# electron_v009.net
KiCad netlist of a schematic drawn in EAGLE
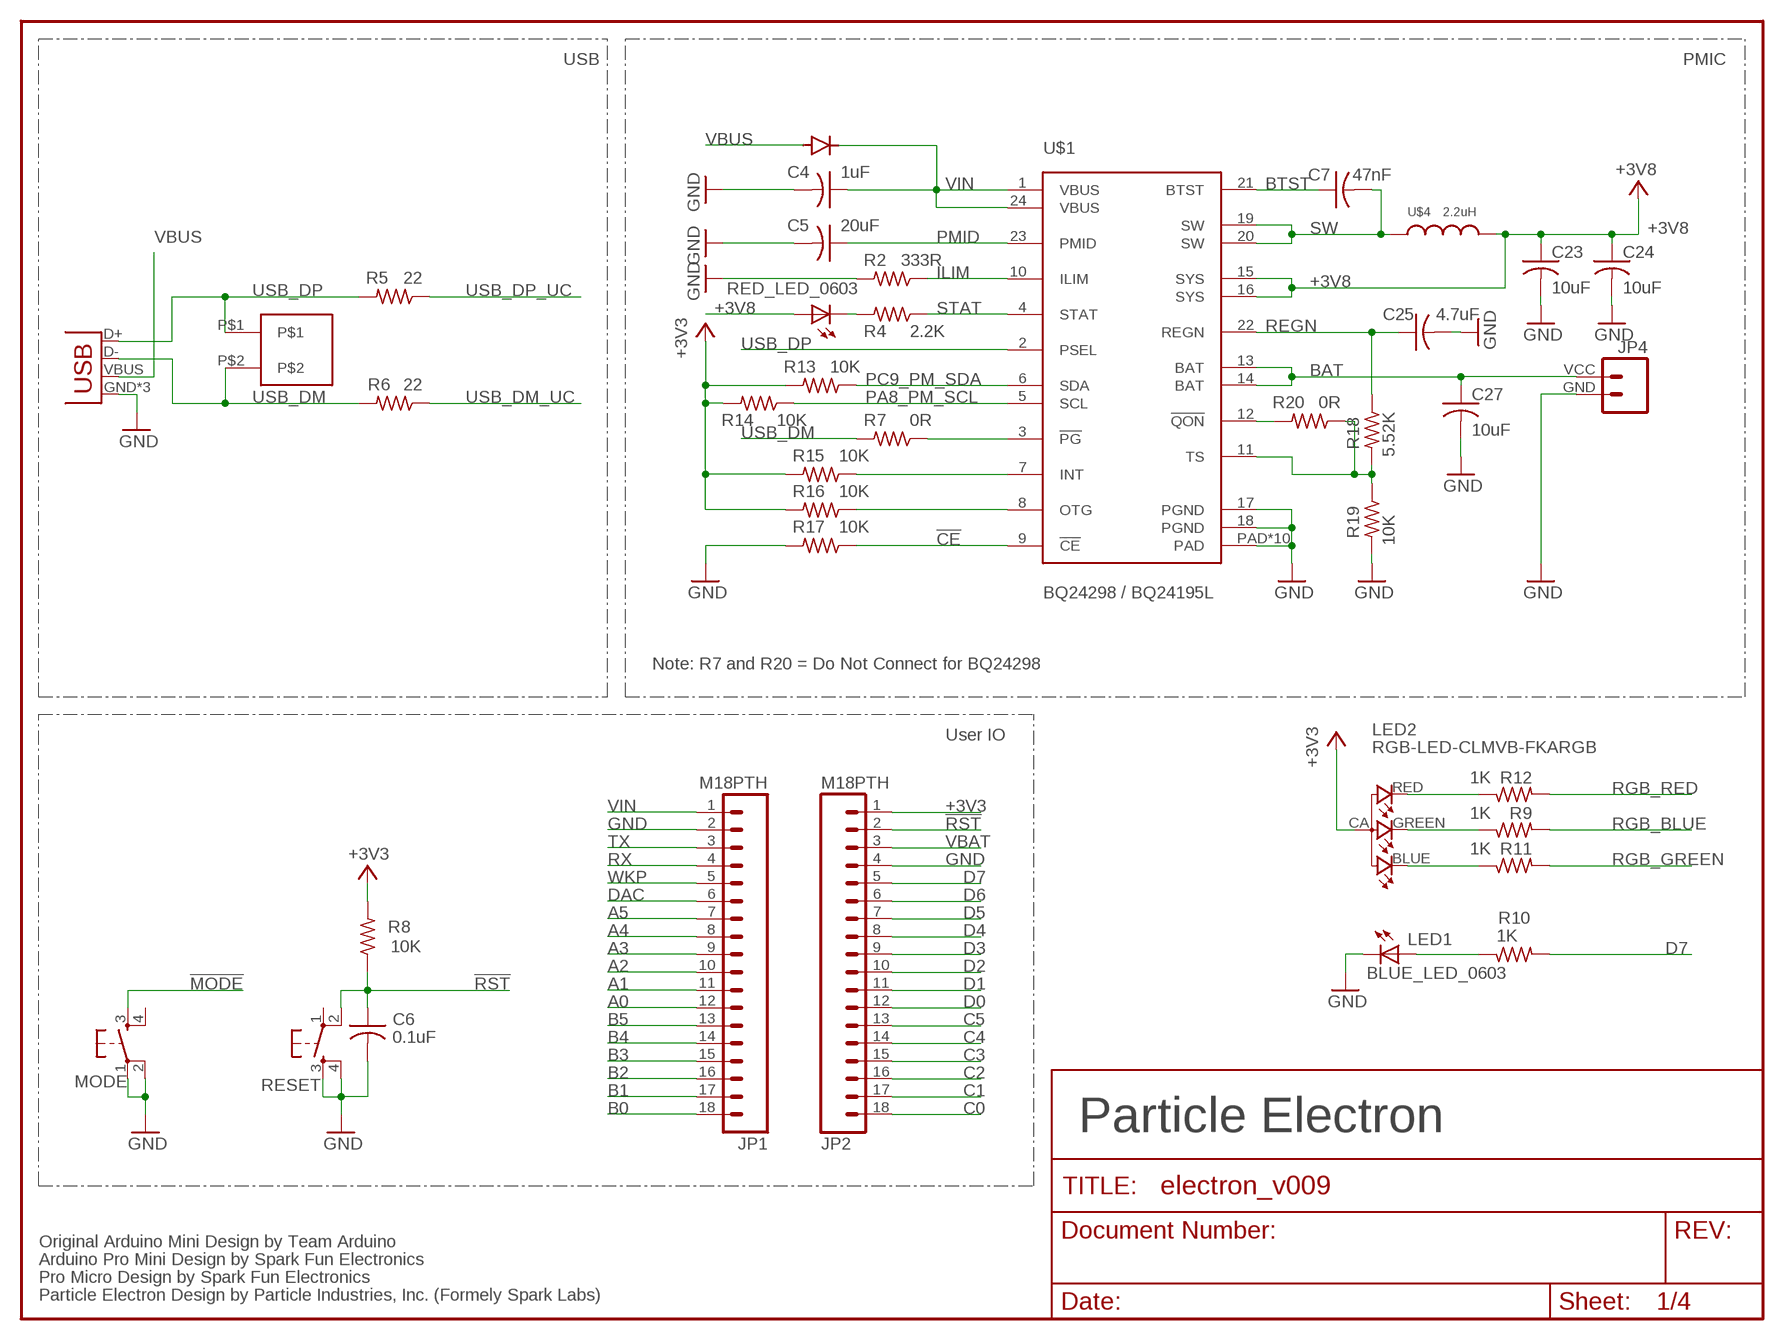
[diagram p0: schematic, sheet 1]
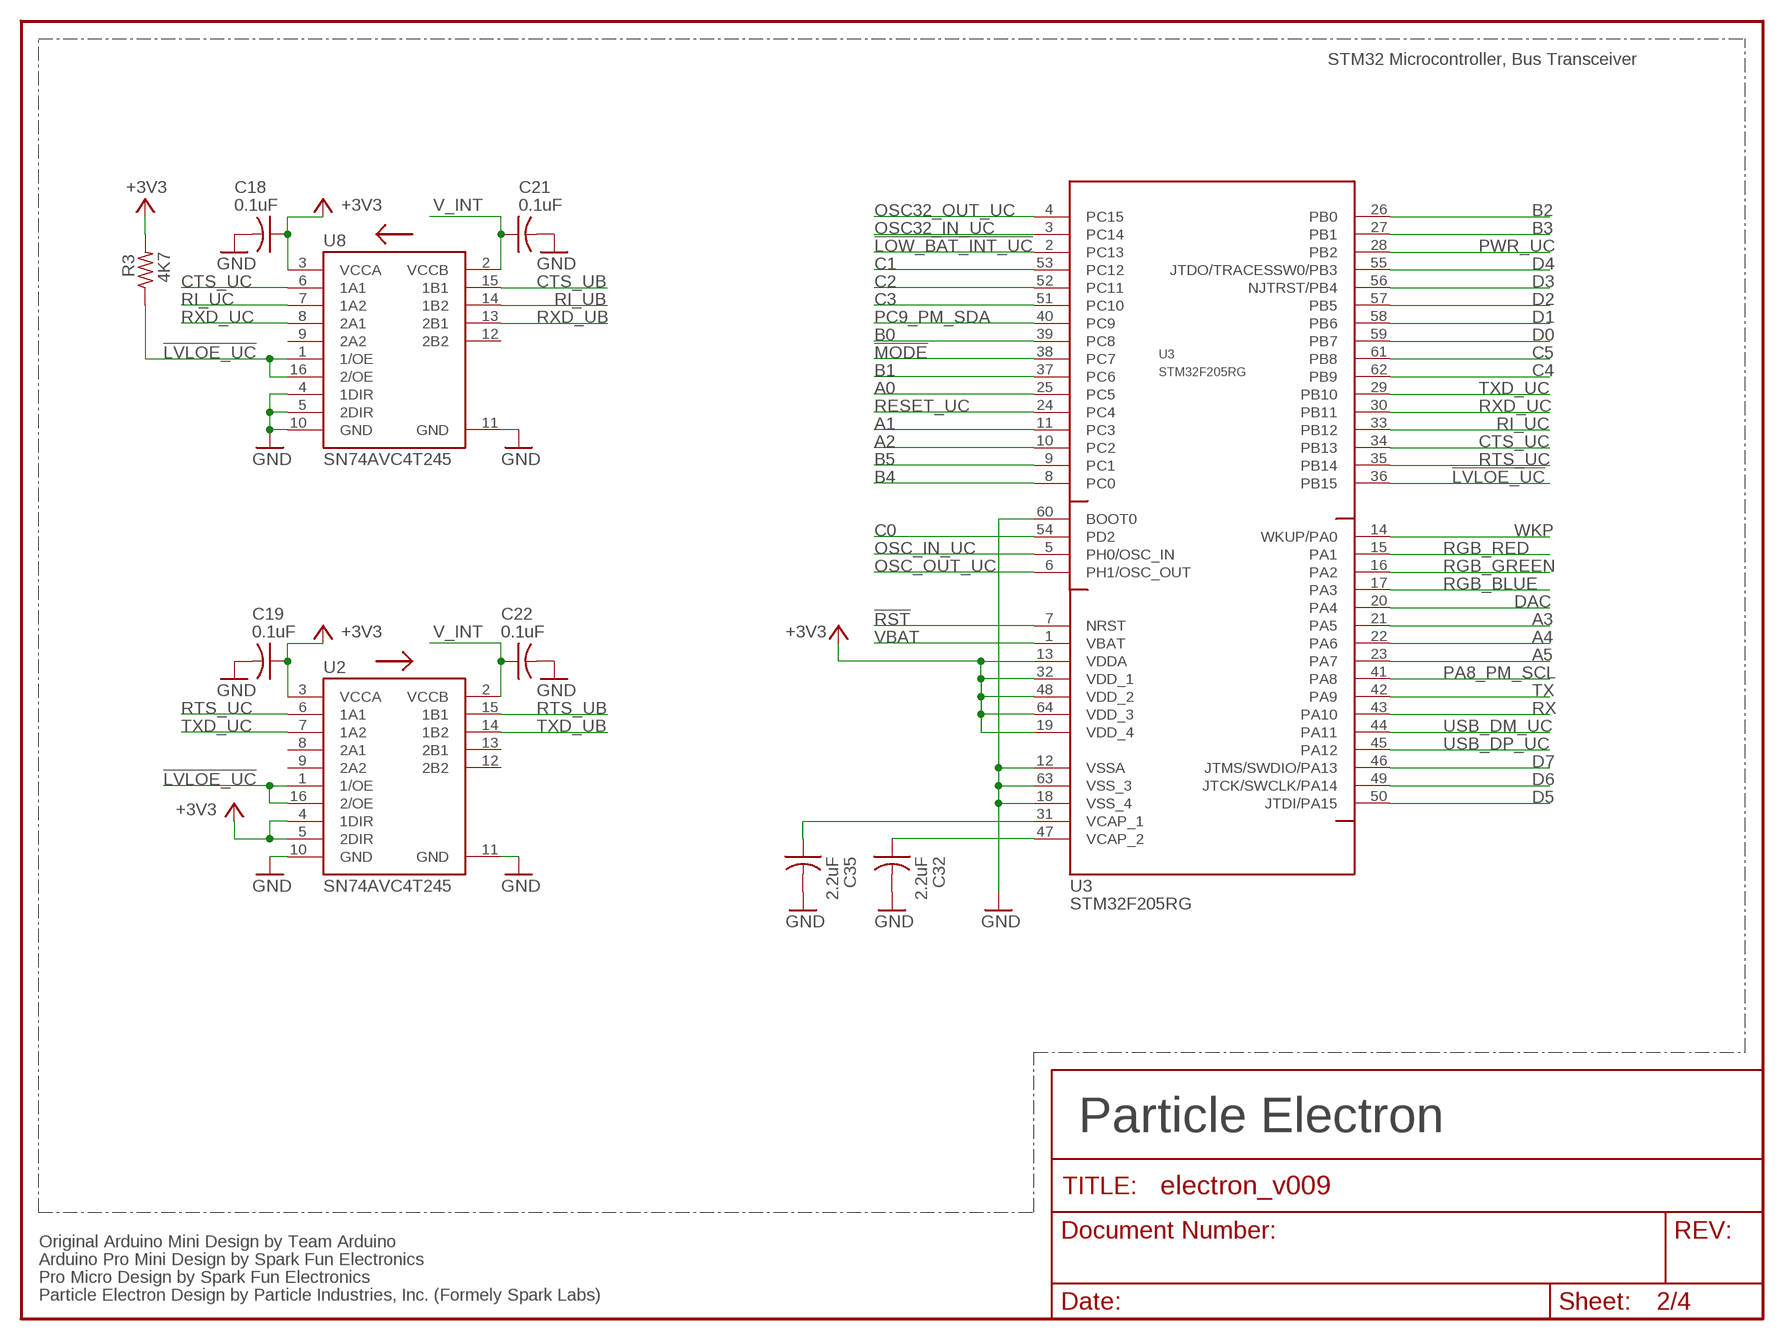
[diagram p1: schematic, sheet 2]
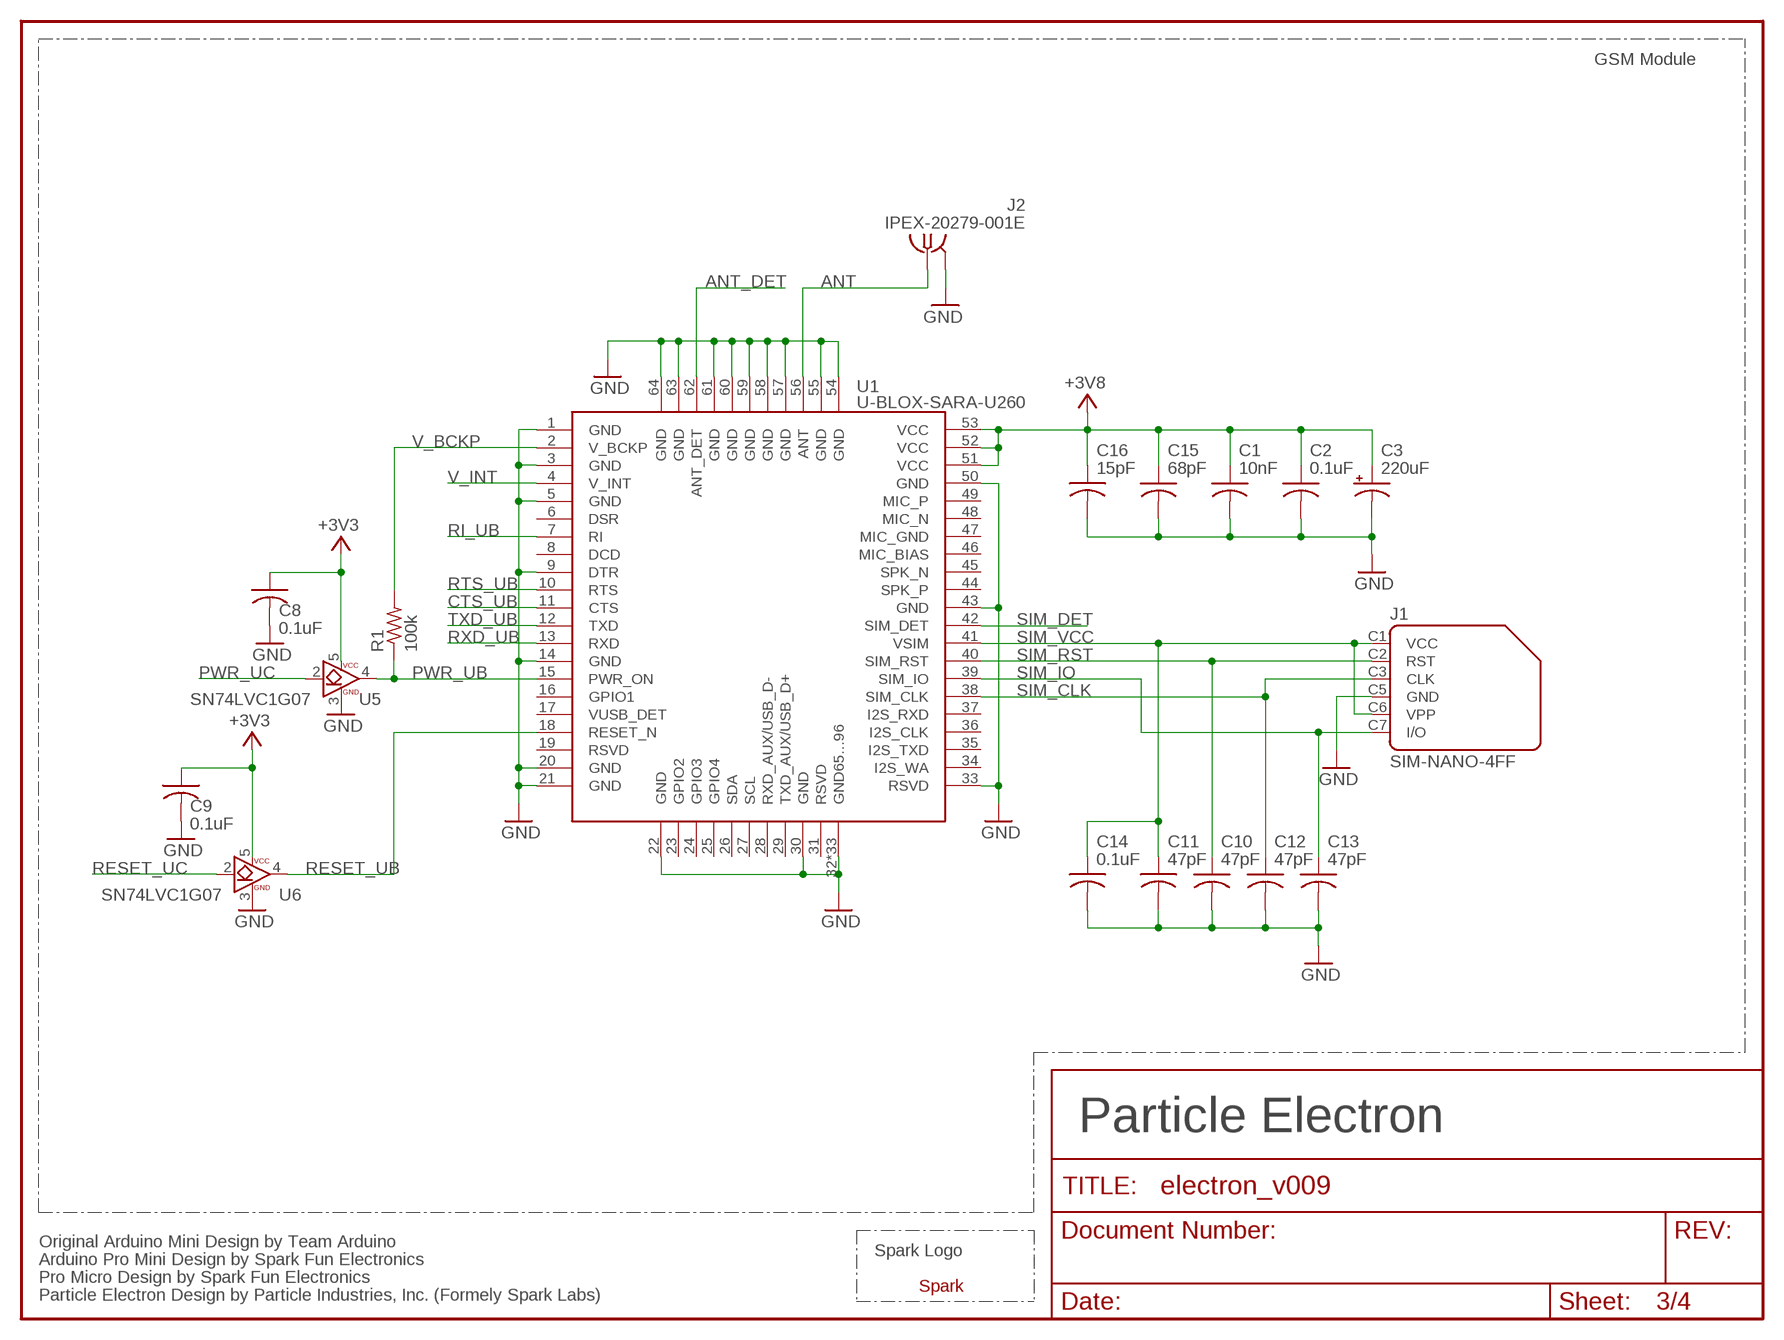
[diagram p2: schematic, sheet 3]
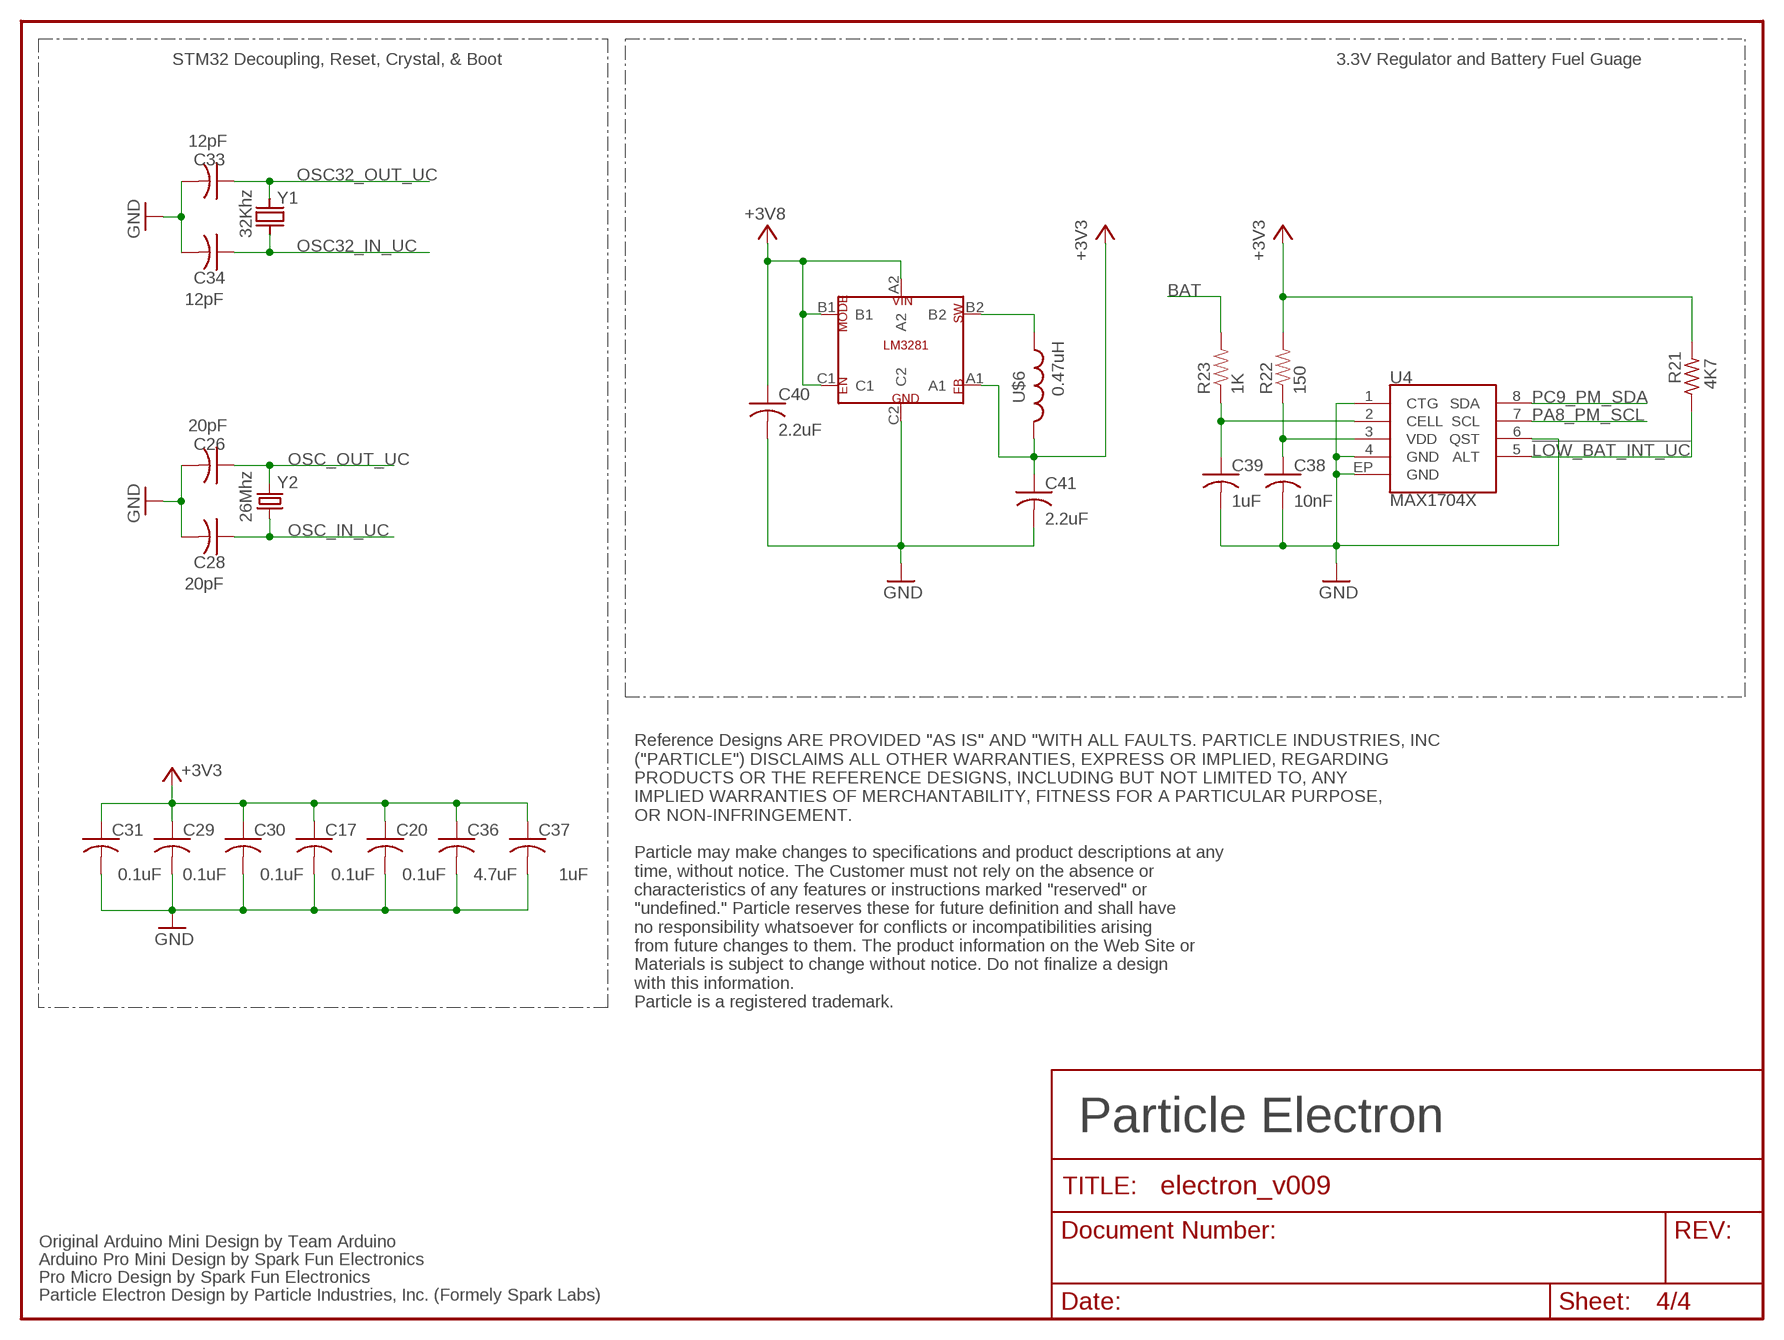
[diagram p3: schematic, sheet 4]

(export (version "E")
  (design (tool "Eeschema 10.0.6"))
  (components
    (comp (ref "C17")
      (value "0.1uF")
      (footprint "eagle-import:C0402_B")
      (libsource (lib "eagle-import") (part "C-US"))
    )
    (comp (ref "C20")
      (value "0.1uF")
      (footprint "eagle-import:C0402_B")
      (libsource (lib "eagle-import") (part "C-US"))
    )
    (comp (ref "C26")
      (value "20pF")
      (footprint "eagle-import:C0402_B")
      (libsource (lib "eagle-import") (part "C-US"))
    )
    (comp (ref "C28")
      (value "20pF")
      (footprint "eagle-import:C0402_B")
      (libsource (lib "eagle-import") (part "C-US"))
    )
    (comp (ref "C29")
      (value "0.1uF")
      (footprint "eagle-import:C0402_B")
      (libsource (lib "eagle-import") (part "C-US"))
    )
    (comp (ref "C30")
      (value "0.1uF")
      (footprint "eagle-import:C0402_B")
      (libsource (lib "eagle-import") (part "C-US"))
    )
    (comp (ref "C31")
      (value "0.1uF")
      (footprint "eagle-import:C0402_B")
      (libsource (lib "eagle-import") (part "C-US"))
    )
    (comp (ref "C33")
      (value "12pF")
      (footprint "eagle-import:C0402_B")
      (libsource (lib "eagle-import") (part "C-US"))
    )
    (comp (ref "C34")
      (value "12pF")
      (footprint "eagle-import:C0402_B")
      (libsource (lib "eagle-import") (part "C-US"))
    )
    (comp (ref "C36")
      (value "4.7uF")
      (footprint "eagle-import:C0402_B")
      (libsource (lib "eagle-import") (part "C-US"))
    )
    (comp (ref "C37")
      (value "1uF")
      (footprint "eagle-import:C0402_B")
      (libsource (lib "eagle-import") (part "C-US"))
    )
    (comp (ref "C38")
      (value "10nF")
      (footprint "eagle-import:C0402_B")
      (libsource (lib "eagle-import") (part "C-US"))
    )
    (comp (ref "C39")
      (value "1uF")
      (footprint "eagle-import:C0402_B")
      (libsource (lib "eagle-import") (part "C-US"))
    )
    (comp (ref "C40")
      (value "2.2uF")
      (footprint "eagle-import:C0603_B")
      (libsource (lib "eagle-import") (part "C-US0603"))
    )
    (comp (ref "C41")
      (value "2.2uF")
      (footprint "eagle-import:C0603_B")
      (libsource (lib "eagle-import") (part "C-US0603"))
    )
    (comp (ref "R21")
      (value "4K7")
      (footprint "eagle-import:R0402_B")
      (libsource (lib "eagle-import") (part "R-US_"))
    )
    (comp (ref "R22")
      (value "150")
      (footprint "eagle-import:0603-RES")
      (libsource (lib "eagle-import") (part "RESISTOR0603-RES"))
    )
    (comp (ref "R23")
      (value "1K")
      (footprint "eagle-import:0603-RES")
      (libsource (lib "eagle-import") (part "RESISTOR0603-RES"))
    )
    (comp (ref "U$5")
      (value "LM3281_DSBGA")
      (footprint "eagle-import:DSBGA")
      (libsource (lib "eagle-import") (part "LM3281_DSBGA"))
    )
    (comp (ref "U$6")
      (value "0.47uH")
      (footprint "eagle-import:0805")
      (libsource (lib "eagle-import") (part "INDUCTOR0805"))
    )
    (comp (ref "U4")
      (value "MAX1704X")
      (footprint "eagle-import:TDFN-8")
      (libsource (lib "eagle-import") (part "MAX1704X"))
    )
    (comp (ref "Y1")
      (value "32Khz")
      (footprint "eagle-import:FC135")
      (libsource (lib "eagle-import") (part "Q_FC135"))
    )
    (comp (ref "Y2")
      (value "26Mhz")
      (footprint "eagle-import:CRYSTAL-SMD-5X3")
      (libsource (lib "eagle-import") (part "CRYSTAL5X3"))
    )
    (comp (ref "C1")
      (value "10nF")
      (footprint "eagle-import:C0402_B")
      (libsource (lib "eagle-import") (part "C-US"))
    )
    (comp (ref "C2")
      (value "0.1uF")
      (footprint "eagle-import:C0402_B")
      (libsource (lib "eagle-import") (part "C-US"))
    )
    (comp (ref "C3")
      (value "220uF")
      (footprint "eagle-import:C_6032-28R")
      (libsource (lib "eagle-import") (part "CPOL-USC/6032-28R"))
    )
    (comp (ref "C8")
      (value "0.1uF")
      (footprint "eagle-import:C0402_B")
      (libsource (lib "eagle-import") (part "C-US"))
    )
    (comp (ref "C9")
      (value "0.1uF")
      (footprint "eagle-import:C0402_B")
      (libsource (lib "eagle-import") (part "C-US"))
    )
    (comp (ref "C10")
      (value "47pF")
      (footprint "eagle-import:C0402_B")
      (libsource (lib "eagle-import") (part "C-US"))
    )
    (comp (ref "C11")
      (value "47pF")
      (footprint "eagle-import:C0402_B")
      (libsource (lib "eagle-import") (part "C-US"))
    )
    (comp (ref "C12")
      (value "47pF")
      (footprint "eagle-import:C0402_B")
      (libsource (lib "eagle-import") (part "C-US"))
    )
    (comp (ref "C13")
      (value "47pF")
      (footprint "eagle-import:C0402_B")
      (libsource (lib "eagle-import") (part "C-US"))
    )
    (comp (ref "C14")
      (value "0.1uF")
      (footprint "eagle-import:C0402_B")
      (libsource (lib "eagle-import") (part "C-US"))
    )
    (comp (ref "C15")
      (value "68pF")
      (footprint "eagle-import:C0402_B")
      (libsource (lib "eagle-import") (part "C-US"))
    )
    (comp (ref "C16")
      (value "15pF")
      (footprint "eagle-import:C0402_B")
      (libsource (lib "eagle-import") (part "C-US"))
    )
    (comp (ref "J1")
      (value "SIM-NANO-4FF")
      (footprint "eagle-import:GCT-SIM8100")
      (libsource (lib "eagle-import") (part "SIM-NANO-4FF"))
    )
    (comp (ref "J2")
      (value "IPEX-20279-001E")
      (footprint "eagle-import:IPEX-20279-001E")
      (libsource (lib "eagle-import") (part "IPEX-20279-001E"))
    )
    (comp (ref "R1")
      (value "100k")
      (footprint "eagle-import:R0402_B")
      (libsource (lib "eagle-import") (part "R-US_"))
    )
    (comp (ref "U$2")
      (value "SPARK_LOGO2")
      (footprint "eagle-import:SPARK_LOGO2")
      (libsource (lib "eagle-import") (part "SPARK_LOGO2"))
    )
    (comp (ref "U1")
      (value "U-BLOX-SARA-U260")
      (footprint "eagle-import:U-BLOX-SARA-U2")
      (libsource (lib "eagle-import") (part "U-BLOX-SARA-U260"))
    )
    (comp (ref "U5")
      (value "SN74LVC1G07")
      (footprint "eagle-import:SC-70-5")
      (libsource (lib "eagle-import") (part "SN74LVC1G07"))
    )
    (comp (ref "U6")
      (value "SN74LVC1G07")
      (footprint "eagle-import:SC-70-5")
      (libsource (lib "eagle-import") (part "SN74LVC1G07"))
    )
    (comp (ref "C18")
      (value "0.1uF")
      (footprint "eagle-import:C0402_B")
      (libsource (lib "eagle-import") (part "C-US"))
    )
    (comp (ref "C19")
      (value "0.1uF")
      (footprint "eagle-import:C0402_B")
      (libsource (lib "eagle-import") (part "C-US"))
    )
    (comp (ref "C21")
      (value "0.1uF")
      (footprint "eagle-import:C0402_B")
      (libsource (lib "eagle-import") (part "C-US"))
    )
    (comp (ref "C22")
      (value "0.1uF")
      (footprint "eagle-import:C0402_B")
      (libsource (lib "eagle-import") (part "C-US"))
    )
    (comp (ref "C32")
      (value "2.2uF")
      (footprint "eagle-import:C0402_B")
      (libsource (lib "eagle-import") (part "C-US"))
    )
    (comp (ref "C35")
      (value "2.2uF")
      (footprint "eagle-import:C0402_B")
      (libsource (lib "eagle-import") (part "C-US"))
    )
    (comp (ref "R3")
      (value "4K7")
      (footprint "eagle-import:R0402_B")
      (libsource (lib "eagle-import") (part "R-US_"))
    )
    (comp (ref "U2")
      (value "SN74AVC4T245")
      (footprint "eagle-import:UFQFN-16")
      (libsource (lib "eagle-import") (part "SN74AVC4T245"))
    )
    (comp (ref "U3")
      (value "STM32F205RG")
      (footprint "eagle-import:LQFP64")
      (libsource (lib "eagle-import") (part "STM32F20XR"))
    )
    (comp (ref "U8")
      (value "SN74AVC4T245")
      (footprint "eagle-import:UFQFN-16")
      (libsource (lib "eagle-import") (part "SN74AVC4T245"))
    )
    (comp (ref "BLUE_LED_0603")
      (value "LED0603")
      (footprint "eagle-import:LED-0603")
      (libsource (lib "eagle-import") (part "LED0603"))
    )
    (comp (ref "C4")
      (value "1uF")
      (footprint "eagle-import:C0603_B")
      (libsource (lib "eagle-import") (part "C-US0603"))
    )
    (comp (ref "C5")
      (value "20uF")
      (footprint "eagle-import:C0603_B")
      (libsource (lib "eagle-import") (part "C-US0603"))
    )
    (comp (ref "C6")
      (value "0.1uF")
      (footprint "eagle-import:C0402_B")
      (libsource (lib "eagle-import") (part "C-US"))
    )
    (comp (ref "C7")
      (value "47nF")
      (footprint "eagle-import:C0402_B")
      (libsource (lib "eagle-import") (part "C-US"))
    )
    (comp (ref "C23")
      (value "10uF")
      (footprint "eagle-import:C0603_B")
      (libsource (lib "eagle-import") (part "C-US0603"))
    )
    (comp (ref "C24")
      (value "10uF")
      (footprint "eagle-import:C0603_B")
      (libsource (lib "eagle-import") (part "C-US0603"))
    )
    (comp (ref "C25")
      (value "4.7uF")
      (footprint "eagle-import:C0603_B")
      (libsource (lib "eagle-import") (part "C-US0603"))
    )
    (comp (ref "C27")
      (value "10uF")
      (footprint "eagle-import:C0603_B")
      (libsource (lib "eagle-import") (part "C-US0603"))
    )
    (comp (ref "JP1")
      (value "M18PTH")
      (footprint "eagle-import:1X18-SMALL-PADS")
      (libsource (lib "eagle-import") (part "M18PTH"))
    )
    (comp (ref "JP2")
      (value "M18PTH")
      (footprint "eagle-import:1X18-SMALL-PADS")
      (libsource (lib "eagle-import") (part "M18PTH"))
    )
    (comp (ref "JP4")
      (value "M024UCON-15767")
      (footprint "eagle-import:JST-2-SMD-VERT")
      (libsource (lib "eagle-import") (part "M024UCON-15767"))
    )
    (comp (ref "LED2")
      (value "RGB-LED-CLMVB-FKARGB")
      (footprint "eagle-import:PLCC4-2MM-RGB")
      (libsource (lib "eagle-import") (part "RGB-LED-CLMVB-FKARGB"))
    )
    (comp (ref "MODE")
      (value "KMR211GLFS")
      (footprint "eagle-import:TACTILE_SWITCH_SMD")
      (libsource (lib "eagle-import") (part "TAC_SWITCHSMD"))
    )
    (comp (ref "R2")
      (value "333R")
      (footprint "eagle-import:R0402_B")
      (libsource (lib "eagle-import") (part "R-US_"))
    )
    (comp (ref "R4")
      (value "2.2K")
      (footprint "eagle-import:R0402_B")
      (libsource (lib "eagle-import") (part "R-US_"))
    )
    (comp (ref "R5")
      (value "22")
      (footprint "eagle-import:R0402_B")
      (libsource (lib "eagle-import") (part "R-US_"))
    )
    (comp (ref "R6")
      (value "22")
      (footprint "eagle-import:R0402_B")
      (libsource (lib "eagle-import") (part "R-US_"))
    )
    (comp (ref "R7")
      (value "0R")
      (footprint "eagle-import:R0402_B")
      (libsource (lib "eagle-import") (part "R-US_"))
    )
    (comp (ref "R8")
      (value "10K")
      (footprint "eagle-import:R0402_B")
      (libsource (lib "eagle-import") (part "R-US_"))
    )
    (comp (ref "R9")
      (value "1K")
      (footprint "eagle-import:R0402_B")
      (libsource (lib "eagle-import") (part "R-US_"))
    )
    (comp (ref "R10")
      (value "1K")
      (footprint "eagle-import:R0402_B")
      (libsource (lib "eagle-import") (part "R-US_"))
    )
    (comp (ref "R11")
      (value "1K")
      (footprint "eagle-import:R0402_B")
      (libsource (lib "eagle-import") (part "R-US_"))
    )
    (comp (ref "R12")
      (value "1K")
      (footprint "eagle-import:R0402_B")
      (libsource (lib "eagle-import") (part "R-US_"))
    )
    (comp (ref "R13")
      (value "10K")
      (footprint "eagle-import:R0402_B")
      (libsource (lib "eagle-import") (part "R-US_"))
    )
    (comp (ref "R14")
      (value "10K")
      (footprint "eagle-import:R0402_B")
      (libsource (lib "eagle-import") (part "R-US_"))
    )
    (comp (ref "R15")
      (value "10K")
      (footprint "eagle-import:R0402_B")
      (libsource (lib "eagle-import") (part "R-US_"))
    )
    (comp (ref "R16")
      (value "10K")
      (footprint "eagle-import:R0402_B")
      (libsource (lib "eagle-import") (part "R-US_"))
    )
    (comp (ref "R17")
      (value "10K")
      (footprint "eagle-import:R0402_B")
      (libsource (lib "eagle-import") (part "R-US_"))
    )
    (comp (ref "R18")
      (value "5.52K")
      (footprint "eagle-import:R0402_B")
      (libsource (lib "eagle-import") (part "R-US_"))
    )
    (comp (ref "R19")
      (value "10K")
      (footprint "eagle-import:R0402_B")
      (libsource (lib "eagle-import") (part "R-US_"))
    )
    (comp (ref "R20")
      (value "0R")
      (footprint "eagle-import:R0402_B")
      (libsource (lib "eagle-import") (part "R-US_"))
    )
    (comp (ref "RED_LED_0603")
      (value "LED0603")
      (footprint "eagle-import:LED-0603")
      (libsource (lib "eagle-import") (part "LED0603"))
    )
    (comp (ref "RESET")
      (value "KMR211GLFS")
      (footprint "eagle-import:TACTILE_SWITCH_SMD")
      (libsource (lib "eagle-import") (part "TAC_SWITCHSMD"))
    )
    (comp (ref "U$1")
      (value "BQ24298 / BQ24195L")
      (footprint "eagle-import:QFN24")
      (libsource (lib "eagle-import") (part "BQ24298RTWR"))
    )
    (comp (ref "U$3")
      (value "DIODE")
      (footprint "eagle-import:DIODE-DO-220AA(SMP)")
      (libsource (lib "eagle-import") (part "DIODE"))
    )
    (comp (ref "U$4")
      (value "2.2uH")
      (footprint "eagle-import:4020TYPE")
      (libsource (lib "eagle-import") (part "INDUCTOR4020"))
    )
    (comp (ref "U$7")
      (value "M02_0.05_HEADER")
      (footprint "eagle-import:M02_0.05_HEADER")
      (libsource (lib "eagle-import") (part "M02_0.05_HEADER"))
    )
    (comp (ref "X1")
      (value "USB-MICROB")
      (footprint "eagle-import:USB-MICROB-SLOT-HOLE")
      (libsource (lib "eagle-import") (part "USBUSB-MICROB-SLOT-HOLE"))
    )
  )
  (nets
    (net (code "1") (name "+3V3") (class "Default")
      (node (ref "C17") (pin "1") (pinfunction "1_1") (pintype "passive"))
      (node (ref "C18") (pin "1") (pinfunction "1_1") (pintype "passive"))
      (node (ref "C19") (pin "1") (pinfunction "1_1") (pintype "passive"))
      (node (ref "C20") (pin "1") (pinfunction "1_1") (pintype "passive"))
      (node (ref "C29") (pin "1") (pinfunction "1_1") (pintype "passive"))
      (node (ref "C30") (pin "1") (pinfunction "1_1") (pintype "passive"))
      (node (ref "C31") (pin "1") (pinfunction "1_1") (pintype "passive"))
      (node (ref "C36") (pin "1") (pinfunction "1_1") (pintype "passive"))
      (node (ref "C37") (pin "1") (pinfunction "1_1") (pintype "passive"))
      (node (ref "C41") (pin "1") (pinfunction "1_1") (pintype "passive"))
      (node (ref "C8") (pin "1") (pinfunction "1_1") (pintype "passive"))
      (node (ref "C9") (pin "1") (pinfunction "1_1") (pintype "passive"))
      (node (ref "JP2") (pin "1") (pinfunction "1_1") (pintype "passive"))
      (node (ref "LED2") (pin "CA") (pinfunction "1_CA") (pintype "passive"))
      (node (ref "R13") (pin "2") (pinfunction "2_2") (pintype "passive"))
      (node (ref "R14") (pin "2") (pinfunction "2_2") (pintype "passive"))
      (node (ref "R15") (pin "2") (pinfunction "2_2") (pintype "passive"))
      (node (ref "R16") (pin "2") (pinfunction "2_2") (pintype "passive"))
      (node (ref "R21") (pin "2") (pinfunction "2_2") (pintype "passive"))
      (node (ref "R22") (pin "2") (pinfunction "2_2") (pintype "passive"))
      (node (ref "R3") (pin "2") (pinfunction "2_2") (pintype "passive"))
      (node (ref "R8") (pin "2") (pinfunction "2_2") (pintype "passive"))
      (node (ref "U$5") (pin "A1") (pinfunction "A1_A1") (pintype "bidirectional"))
      (node (ref "U$6") (pin "2") (pinfunction "2_2") (pintype "passive"))
      (node (ref "U2") (pin "3") (pinfunction "VCCA_3") (pintype "bidirectional"))
      (node (ref "U2") (pin "4") (pinfunction "1DIR_4") (pintype "bidirectional"))
      (node (ref "U2") (pin "5") (pinfunction "2DIR_5") (pintype "bidirectional"))
      (node (ref "U3") (pin "13") (pinfunction "VDDA_13") (pintype "power_in"))
      (node (ref "U3") (pin "19") (pinfunction "VDD_4_19") (pintype "power_in"))
      (node (ref "U3") (pin "32") (pinfunction "VDD_1_32") (pintype "power_in"))
      (node (ref "U3") (pin "48") (pinfunction "VDD_2_48") (pintype "power_in"))
      (node (ref "U3") (pin "64") (pinfunction "VDD_3_64") (pintype "power_in"))
      (node (ref "U5") (pin "5") (pinfunction "VCC_5") (pintype "bidirectional"))
      (node (ref "U6") (pin "5") (pinfunction "VCC_5") (pintype "bidirectional"))
      (node (ref "U8") (pin "3") (pinfunction "VCCA_3") (pintype "bidirectional"))
    )
    (net (code "2") (name "+3V8") (class "Default")
      (node (ref "C1") (pin "1") (pinfunction "1_1") (pintype "passive"))
      (node (ref "C15") (pin "1") (pinfunction "1_1") (pintype "passive"))
      (node (ref "C16") (pin "1") (pinfunction "1_1") (pintype "passive"))
      (node (ref "C2") (pin "1") (pinfunction "1_1") (pintype "passive"))
      (node (ref "C23") (pin "1") (pinfunction "1_1") (pintype "passive"))
      (node (ref "C24") (pin "1") (pinfunction "1_1") (pintype "passive"))
      (node (ref "C3") (pin "+") (pinfunction "+_+") (pintype "passive"))
      (node (ref "C40") (pin "1") (pinfunction "1_1") (pintype "passive"))
      (node (ref "RED_LED_0603") (pin "A") (pinfunction "A_A") (pintype "passive"))
      (node (ref "U$1") (pin "15") (pinfunction "SYS_15") (pintype "power_in"))
      (node (ref "U$1") (pin "16") (pinfunction "SYS_16") (pintype "power_in"))
      (node (ref "U$4") (pin "P$2") (pinfunction "2_P$2") (pintype "bidirectional"))
      (node (ref "U$5") (pin "A2") (pinfunction "A2_A2") (pintype "bidirectional"))
      (node (ref "U$5") (pin "B1") (pinfunction "B1_B1") (pintype "bidirectional"))
      (node (ref "U$5") (pin "C1") (pinfunction "C1_C1") (pintype "bidirectional"))
      (node (ref "U1") (pin "51") (pinfunction "VCC_51") (pintype "bidirectional"))
      (node (ref "U1") (pin "52") (pinfunction "VCC_52") (pintype "bidirectional"))
      (node (ref "U1") (pin "53") (pinfunction "VCC_53") (pintype "bidirectional"))
    )
    (net (code "3") (name "A0") (class "Default")
      (node (ref "JP1") (pin "12") (pinfunction "12_12") (pintype "passive"))
      (node (ref "U3") (pin "25") (pinfunction "PC5_25") (pintype "bidirectional"))
    )
    (net (code "4") (name "A1") (class "Default")
      (node (ref "JP1") (pin "11") (pinfunction "11_11") (pintype "passive"))
      (node (ref "U3") (pin "11") (pinfunction "PC3_11") (pintype "bidirectional"))
    )
    (net (code "5") (name "A2") (class "Default")
      (node (ref "JP1") (pin "10") (pinfunction "10_10") (pintype "passive"))
      (node (ref "U3") (pin "10") (pinfunction "PC2_10") (pintype "bidirectional"))
    )
    (net (code "6") (name "A3") (class "Default")
      (node (ref "JP1") (pin "9") (pinfunction "9_9") (pintype "passive"))
      (node (ref "U3") (pin "21") (pinfunction "PA5_21") (pintype "bidirectional"))
    )
    (net (code "7") (name "A4") (class "Default")
      (node (ref "JP1") (pin "8") (pinfunction "8_8") (pintype "passive"))
      (node (ref "U3") (pin "22") (pinfunction "PA6_22") (pintype "bidirectional"))
    )
    (net (code "8") (name "A5") (class "Default")
      (node (ref "JP1") (pin "7") (pinfunction "7_7") (pintype "passive"))
      (node (ref "U3") (pin "23") (pinfunction "PA7_23") (pintype "bidirectional"))
    )
    (net (code "9") (name "ANT") (class "Default")
      (node (ref "J2") (pin "1") (pinfunction "1_1") (pintype "passive"))
      (node (ref "U1") (pin "56") (pinfunction "ANT_56") (pintype "bidirectional"))
    )
    (net (code "10") (name "ANT_DET") (class "Default")
      (node (ref "U1") (pin "62") (pinfunction "ANT_DET_62") (pintype "bidirectional"))
    )
    (net (code "11") (name "B0") (class "Default")
      (node (ref "JP1") (pin "18") (pinfunction "18_18") (pintype "passive"))
      (node (ref "U3") (pin "39") (pinfunction "PC8_39") (pintype "bidirectional"))
    )
    (net (code "12") (name "B1") (class "Default")
      (node (ref "JP1") (pin "17") (pinfunction "17_17") (pintype "passive"))
      (node (ref "U3") (pin "37") (pinfunction "PC6_37") (pintype "bidirectional"))
    )
    (net (code "13") (name "B2") (class "Default")
      (node (ref "JP1") (pin "16") (pinfunction "16_16") (pintype "passive"))
      (node (ref "U3") (pin "26") (pinfunction "PB0_26") (pintype "bidirectional"))
    )
    (net (code "14") (name "B3") (class "Default")
      (node (ref "JP1") (pin "15") (pinfunction "15_15") (pintype "passive"))
      (node (ref "U3") (pin "27") (pinfunction "PB1_27") (pintype "bidirectional"))
    )
    (net (code "15") (name "B4") (class "Default")
      (node (ref "JP1") (pin "14") (pinfunction "14_14") (pintype "passive"))
      (node (ref "U3") (pin "8") (pinfunction "PC0_8") (pintype "bidirectional"))
    )
    (net (code "16") (name "B5") (class "Default")
      (node (ref "JP1") (pin "13") (pinfunction "13_13") (pintype "passive"))
      (node (ref "U3") (pin "9") (pinfunction "PC1_9") (pintype "bidirectional"))
    )
    (net (code "17") (name "BAT") (class "Default")
      (node (ref "C27") (pin "1") (pinfunction "1_1") (pintype "passive"))
      (node (ref "JP4") (pin "VCC") (pinfunction "2_VCC") (pintype "passive"))
      (node (ref "R23") (pin "2") (pinfunction "2_2") (pintype "passive"))
      (node (ref "U$1") (pin "13") (pinfunction "BAT_13") (pintype "passive"))
      (node (ref "U$1") (pin "14") (pinfunction "BAT_14") (pintype "power_in"))
    )
    (net (code "18") (name "BTST") (class "Default")
      (node (ref "C7") (pin "1") (pinfunction "1_1") (pintype "passive"))
      (node (ref "U$1") (pin "21") (pinfunction "BTST_21") (pintype "bidirectional"))
    )
    (net (code "19") (name "C0") (class "Default")
      (node (ref "JP2") (pin "18") (pinfunction "18_18") (pintype "passive"))
      (node (ref "U3") (pin "54") (pinfunction "PD2_54") (pintype "bidirectional"))
    )
    (net (code "20") (name "C1") (class "Default")
      (node (ref "JP2") (pin "17") (pinfunction "17_17") (pintype "passive"))
      (node (ref "U3") (pin "53") (pinfunction "PC12_53") (pintype "bidirectional"))
    )
    (net (code "21") (name "C2") (class "Default")
      (node (ref "JP2") (pin "16") (pinfunction "16_16") (pintype "passive"))
      (node (ref "U3") (pin "52") (pinfunction "PC11_52") (pintype "bidirectional"))
    )
    (net (code "22") (name "C3") (class "Default")
      (node (ref "JP2") (pin "15") (pinfunction "15_15") (pintype "passive"))
      (node (ref "U3") (pin "51") (pinfunction "PC10_51") (pintype "bidirectional"))
    )
    (net (code "23") (name "C4") (class "Default")
      (node (ref "JP2") (pin "14") (pinfunction "14_14") (pintype "passive"))
      (node (ref "U3") (pin "62") (pinfunction "PB9_62") (pintype "bidirectional"))
    )
    (net (code "24") (name "C5") (class "Default")
      (node (ref "JP2") (pin "13") (pinfunction "13_13") (pintype "passive"))
      (node (ref "U3") (pin "61") (pinfunction "PB8_61") (pintype "bidirectional"))
    )
    (net (code "25") (name "CTS_UB") (class "Default")
      (node (ref "U1") (pin "11") (pinfunction "CTS_11") (pintype "bidirectional"))
      (node (ref "U8") (pin "15") (pinfunction "1B1_15") (pintype "bidirectional"))
    )
    (net (code "26") (name "CTS_UC") (class "Default")
      (node (ref "U3") (pin "34") (pinfunction "PB13_34") (pintype "bidirectional"))
      (node (ref "U8") (pin "6") (pinfunction "1A1_6") (pintype "bidirectional"))
    )
    (net (code "27") (name "D0") (class "Default")
      (node (ref "JP2") (pin "12") (pinfunction "12_12") (pintype "passive"))
      (node (ref "U3") (pin "59") (pinfunction "PB7_59") (pintype "bidirectional"))
    )
    (net (code "28") (name "D1") (class "Default")
      (node (ref "JP2") (pin "11") (pinfunction "11_11") (pintype "passive"))
      (node (ref "U3") (pin "58") (pinfunction "PB6_58") (pintype "bidirectional"))
    )
    (net (code "29") (name "D2") (class "Default")
      (node (ref "JP2") (pin "10") (pinfunction "10_10") (pintype "passive"))
      (node (ref "U3") (pin "57") (pinfunction "PB5_57") (pintype "bidirectional"))
    )
    (net (code "30") (name "D3") (class "Default")
      (node (ref "JP2") (pin "9") (pinfunction "9_9") (pintype "passive"))
      (node (ref "U3") (pin "56") (pinfunction "NJTRST/PB4_56") (pintype "bidirectional"))
    )
    (net (code "31") (name "D4") (class "Default")
      (node (ref "JP2") (pin "8") (pinfunction "8_8") (pintype "passive"))
      (node (ref "U3") (pin "55") (pinfunction "JTDO/TRACESSW0/PB3_55") (pintype "bidirectional"))
    )
    (net (code "32") (name "D5") (class "Default")
      (node (ref "JP2") (pin "7") (pinfunction "7_7") (pintype "passive"))
      (node (ref "U3") (pin "50") (pinfunction "JTDI/PA15_50") (pintype "bidirectional"))
    )
    (net (code "33") (name "D6") (class "Default")
      (node (ref "JP2") (pin "6") (pinfunction "6_6") (pintype "passive"))
      (node (ref "U3") (pin "49") (pinfunction "JTCK/SWCLK/PA14_49") (pintype "bidirectional"))
    )
    (net (code "34") (name "D7") (class "Default")
      (node (ref "JP2") (pin "5") (pinfunction "5_5") (pintype "passive"))
      (node (ref "R10") (pin "2") (pinfunction "2_2") (pintype "passive"))
      (node (ref "U3") (pin "46") (pinfunction "JTMS/SWDIO/PA13_46") (pintype "bidirectional"))
    )
    (net (code "35") (name "DAC") (class "Default")
      (node (ref "JP1") (pin "6") (pinfunction "6_6") (pintype "passive"))
      (node (ref "U3") (pin "20") (pinfunction "PA4_20") (pintype "bidirectional"))
    )
    (net (code "36") (name "GND") (class "Default")
      (node (ref "BLUE_LED_0603") (pin "C") (pinfunction "C_C") (pintype "passive"))
      (node (ref "C1") (pin "2") (pinfunction "2_2") (pintype "passive"))
      (node (ref "C10") (pin "2") (pinfunction "2_2") (pintype "passive"))
      (node (ref "C11") (pin "2") (pinfunction "2_2") (pintype "passive"))
      (node (ref "C12") (pin "2") (pinfunction "2_2") (pintype "passive"))
      (node (ref "C13") (pin "2") (pinfunction "2_2") (pintype "passive"))
      (node (ref "C14") (pin "2") (pinfunction "2_2") (pintype "passive"))
      (node (ref "C15") (pin "2") (pinfunction "2_2") (pintype "passive"))
      (node (ref "C16") (pin "2") (pinfunction "2_2") (pintype "passive"))
      (node (ref "C17") (pin "2") (pinfunction "2_2") (pintype "passive"))
      (node (ref "C18") (pin "2") (pinfunction "2_2") (pintype "passive"))
      (node (ref "C19") (pin "2") (pinfunction "2_2") (pintype "passive"))
      (node (ref "C2") (pin "2") (pinfunction "2_2") (pintype "passive"))
      (node (ref "C20") (pin "2") (pinfunction "2_2") (pintype "passive"))
      (node (ref "C21") (pin "2") (pinfunction "2_2") (pintype "passive"))
      (node (ref "C22") (pin "2") (pinfunction "2_2") (pintype "passive"))
      (node (ref "C23") (pin "2") (pinfunction "2_2") (pintype "passive"))
      (node (ref "C24") (pin "2") (pinfunction "2_2") (pintype "passive"))
      (node (ref "C25") (pin "2") (pinfunction "2_2") (pintype "passive"))
      (node (ref "C26") (pin "2") (pinfunction "2_2") (pintype "passive"))
      (node (ref "C27") (pin "2") (pinfunction "2_2") (pintype "passive"))
      (node (ref "C28") (pin "2") (pinfunction "2_2") (pintype "passive"))
      (node (ref "C29") (pin "2") (pinfunction "2_2") (pintype "passive"))
      (node (ref "C3") (pin "-") (pinfunction "-_-") (pintype "passive"))
      (node (ref "C30") (pin "2") (pinfunction "2_2") (pintype "passive"))
      (node (ref "C31") (pin "2") (pinfunction "2_2") (pintype "passive"))
      (node (ref "C32") (pin "2") (pinfunction "2_2") (pintype "passive"))
      (node (ref "C33") (pin "2") (pinfunction "2_2") (pintype "passive"))
      (node (ref "C34") (pin "2") (pinfunction "2_2") (pintype "passive"))
      (node (ref "C35") (pin "2") (pinfunction "2_2") (pintype "passive"))
      (node (ref "C36") (pin "2") (pinfunction "2_2") (pintype "passive"))
      (node (ref "C37") (pin "2") (pinfunction "2_2") (pintype "passive"))
      (node (ref "C38") (pin "2") (pinfunction "2_2") (pintype "passive"))
      (node (ref "C39") (pin "2") (pinfunction "2_2") (pintype "passive"))
      (node (ref "C4") (pin "2") (pinfunction "2_2") (pintype "passive"))
      (node (ref "C40") (pin "2") (pinfunction "2_2") (pintype "passive"))
      (node (ref "C41") (pin "2") (pinfunction "2_2") (pintype "passive"))
      (node (ref "C5") (pin "2") (pinfunction "2_2") (pintype "passive"))
      (node (ref "C6") (pin "2") (pinfunction "2_2") (pintype "passive"))
      (node (ref "C8") (pin "2") (pinfunction "2_2") (pintype "passive"))
      (node (ref "C9") (pin "2") (pinfunction "2_2") (pintype "passive"))
      (node (ref "J1") (pin "C5") (pinfunction "GND_C5") (pintype "passive"))
      (node (ref "J2") (pin "2@1") (pinfunction "GND_2@1") (pintype "passive"))
      (node (ref "J2") (pin "2@2") (pinfunction "GND_2@2") (pintype "passive"))
      (node (ref "JP1") (pin "2") (pinfunction "2_2") (pintype "passive"))
      (node (ref "JP2") (pin "4") (pinfunction "4_4") (pintype "passive"))
      (node (ref "JP4") (pin "GND") (pinfunction "1_GND") (pintype "passive"))
      (node (ref "MODE") (pin "1") (pinfunction "1_1") (pintype "passive"))
      (node (ref "MODE") (pin "2") (pinfunction "2_2") (pintype "passive"))
      (node (ref "R17") (pin "2") (pinfunction "2_2") (pintype "passive"))
      (node (ref "R19") (pin "2") (pinfunction "2_2") (pintype "passive"))
      (node (ref "R2") (pin "2") (pinfunction "2_2") (pintype "passive"))
      (node (ref "RESET") (pin "3") (pinfunction "3_3") (pintype "passive"))
      (node (ref "RESET") (pin "4") (pinfunction "4_4") (pintype "passive"))
      (node (ref "U$1") (pin "17") (pinfunction "PGND_17") (pintype "passive"))
      (node (ref "U$1") (pin "18") (pinfunction "PGND_18") (pintype "passive"))
      (node (ref "U$1") (pin "PAD") (pinfunction "PAD_PAD") (pintype "power_in"))
      (node (ref "U$1") (pin "PAD@1") (pinfunction "PAD_PAD@1") (pintype "power_in"))
      (node (ref "U$1") (pin "PAD@2") (pinfunction "PAD_PAD@2") (pintype "power_in"))
      (node (ref "U$1") (pin "PAD@3") (pinfunction "PAD_PAD@3") (pintype "power_in"))
      (node (ref "U$1") (pin "PAD@4") (pinfunction "PAD_PAD@4") (pintype "power_in"))
      (node (ref "U$1") (pin "PAD@5") (pinfunction "PAD_PAD@5") (pintype "power_in"))
      (node (ref "U$1") (pin "PAD@6") (pinfunction "PAD_PAD@6") (pintype "power_in"))
      (node (ref "U$1") (pin "PAD@7") (pinfunction "PAD_PAD@7") (pintype "power_in"))
      (node (ref "U$1") (pin "PAD@8") (pinfunction "PAD_PAD@8") (pintype "power_in"))
      (node (ref "U$1") (pin "PAD@9") (pinfunction "PAD_PAD@9") (pintype "power_in"))
      (node (ref "U$5") (pin "C2") (pinfunction "C2_C2") (pintype "bidirectional"))
      (node (ref "U1") (pin "1") (pinfunction "GND_1") (pintype "bidirectional"))
      (node (ref "U1") (pin "14") (pinfunction "GND_14") (pintype "bidirectional"))
      (node (ref "U1") (pin "20") (pinfunction "GND_20") (pintype "bidirectional"))
      (node (ref "U1") (pin "21") (pinfunction "GND_21") (pintype "bidirectional"))
      (node (ref "U1") (pin "22") (pinfunction "GND_22") (pintype "bidirectional"))
      (node (ref "U1") (pin "3") (pinfunction "GND_3") (pintype "bidirectional"))
      (node (ref "U1") (pin "30") (pinfunction "GND_30") (pintype "bidirectional"))
      (node (ref "U1") (pin "32") (pinfunction "GND65...96_32") (pintype "bidirectional"))
      (node (ref "U1") (pin "33") (pinfunction "RSVD_33") (pintype "bidirectional"))
      (node (ref "U1") (pin "43") (pinfunction "GND_43") (pintype "bidirectional"))
      (node (ref "U1") (pin "5") (pinfunction "GND_5") (pintype "bidirectional"))
      (node (ref "U1") (pin "50") (pinfunction "GND_50") (pintype "bidirectional"))
      (node (ref "U1") (pin "54") (pinfunction "GND_54") (pintype "bidirectional"))
      (node (ref "U1") (pin "55") (pinfunction "GND_55") (pintype "bidirectional"))
      (node (ref "U1") (pin "57") (pinfunction "GND_57") (pintype "bidirectional"))
      (node (ref "U1") (pin "58") (pinfunction "GND_58") (pintype "bidirectional"))
      (node (ref "U1") (pin "59") (pinfunction "GND_59") (pintype "bidirectional"))
      (node (ref "U1") (pin "60") (pinfunction "GND_60") (pintype "bidirectional"))
      (node (ref "U1") (pin "61") (pinfunction "GND_61") (pintype "bidirectional"))
      (node (ref "U1") (pin "63") (pinfunction "GND_63") (pintype "bidirectional"))
      (node (ref "U1") (pin "64") (pinfunction "GND_64") (pintype "bidirectional"))
      (node (ref "U1") (pin "65") (pinfunction "GND65...96_65") (pintype "bidirectional"))
      (node (ref "U1") (pin "66") (pinfunction "GND65...96_66") (pintype "bidirectional"))
      (node (ref "U1") (pin "67") (pinfunction "GND65...96_67") (pintype "bidirectional"))
      (node (ref "U1") (pin "68") (pinfunction "GND65...96_68") (pintype "bidirectional"))
      (node (ref "U1") (pin "69") (pinfunction "GND65...96_69") (pintype "bidirectional"))
      (node (ref "U1") (pin "70") (pinfunction "GND65...96_70") (pintype "bidirectional"))
      (node (ref "U1") (pin "71") (pinfunction "GND65...96_71") (pintype "bidirectional"))
      (node (ref "U1") (pin "72") (pinfunction "GND65...96_72") (pintype "bidirectional"))
      (node (ref "U1") (pin "73") (pinfunction "GND65...96_73") (pintype "bidirectional"))
      (node (ref "U1") (pin "74") (pinfunction "GND65...96_74") (pintype "bidirectional"))
      (node (ref "U1") (pin "75") (pinfunction "GND65...96_75") (pintype "bidirectional"))
      (node (ref "U1") (pin "76") (pinfunction "GND65...96_76") (pintype "bidirectional"))
      (node (ref "U1") (pin "77") (pinfunction "GND65...96_77") (pintype "bidirectional"))
      (node (ref "U1") (pin "78") (pinfunction "GND65...96_78") (pintype "bidirectional"))
      (node (ref "U1") (pin "79") (pinfunction "GND65...96_79") (pintype "bidirectional"))
      (node (ref "U1") (pin "80") (pinfunction "GND65...96_80") (pintype "bidirectional"))
      (node (ref "U1") (pin "81") (pinfunction "GND65...96_81") (pintype "bidirectional"))
      (node (ref "U1") (pin "82") (pinfunction "GND65...96_82") (pintype "bidirectional"))
      (node (ref "U1") (pin "83") (pinfunction "GND65...96_83") (pintype "bidirectional"))
      (node (ref "U1") (pin "84") (pinfunction "GND65...96_84") (pintype "bidirectional"))
      (node (ref "U1") (pin "85") (pinfunction "GND65...96_85") (pintype "bidirectional"))
      (node (ref "U1") (pin "86") (pinfunction "GND65...96_86") (pintype "bidirectional"))
      (node (ref "U1") (pin "87") (pinfunction "GND65...96_87") (pintype "bidirectional"))
      (node (ref "U1") (pin "88") (pinfunction "GND65...96_88") (pintype "bidirectional"))
      (node (ref "U1") (pin "89") (pinfunction "GND65...96_89") (pintype "bidirectional"))
      (node (ref "U1") (pin "9") (pinfunction "DTR_9") (pintype "bidirectional"))
      (node (ref "U1") (pin "90") (pinfunction "GND65...96_90") (pintype "bidirectional"))
      (node (ref "U1") (pin "91") (pinfunction "GND65...96_91") (pintype "bidirectional"))
      (node (ref "U1") (pin "92") (pinfunction "GND65...96_92") (pintype "bidirectional"))
      (node (ref "U1") (pin "93") (pinfunction "GND65...96_93") (pintype "bidirectional"))
      (node (ref "U1") (pin "94") (pinfunction "GND65...96_94") (pintype "bidirectional"))
      (node (ref "U1") (pin "95") (pinfunction "GND65...96_95") (pintype "bidirectional"))
      (node (ref "U1") (pin "96") (pinfunction "GND65...96_96") (pintype "bidirectional"))
      (node (ref "U2") (pin "10") (pinfunction "GND_10") (pintype "bidirectional"))
      (node (ref "U2") (pin "11") (pinfunction "GND_11") (pintype "bidirectional"))
      (node (ref "U3") (pin "12") (pinfunction "VSSA_12") (pintype "power_in"))
      (node (ref "U3") (pin "18") (pinfunction "VSS_4_18") (pintype "power_in"))
      (node (ref "U3") (pin "60") (pinfunction "BOOT0_60") (pintype "bidirectional"))
      (node (ref "U3") (pin "63") (pinfunction "VSS_3_63") (pintype "power_in"))
      (node (ref "U4") (pin "1") (pinfunction "CTG_1") (pintype "bidirectional"))
      (node (ref "U4") (pin "4") (pinfunction "GND_4") (pintype "bidirectional"))
      (node (ref "U4") (pin "6") (pinfunction "QST_6") (pintype "bidirectional"))
      (node (ref "U4") (pin "EP") (pinfunction "GND_EP") (pintype "bidirectional"))
      (node (ref "U5") (pin "3") (pinfunction "GND_3") (pintype "bidirectional"))
      (node (ref "U6") (pin "3") (pinfunction "GND_3") (pintype "bidirectional"))
      (node (ref "U8") (pin "10") (pinfunction "GND_10") (pintype "bidirectional"))
      (node (ref "U8") (pin "11") (pinfunction "GND_11") (pintype "bidirectional"))
      (node (ref "U8") (pin "4") (pinfunction "1DIR_4") (pintype "bidirectional"))
      (node (ref "U8") (pin "5") (pinfunction "2DIR_5") (pintype "bidirectional"))
      (node (ref "X1") (pin "GND") (pinfunction "GND_GND") (pintype "bidirectional"))
      (node (ref "X1") (pin "MT1") (pinfunction "GND_MT1") (pintype "bidirectional"))
      (node (ref "X1") (pin "MT2") (pinfunction "GND_MT2") (pintype "bidirectional"))
    )
    (net (code "37") (name "ILIM") (class "Default")
      (node (ref "R2") (pin "1") (pinfunction "1_1") (pintype "passive"))
      (node (ref "U$1") (pin "10") (pinfunction "ILIM_10") (pintype "output"))
    )
    (net (code "38") (name "LED1") (class "Default")
      (node (ref "BLUE_LED_0603") (pin "A") (pinfunction "A_A") (pintype "passive"))
      (node (ref "R10") (pin "1") (pinfunction "1_1") (pintype "passive"))
    )
    (net (code "39") (name "Net-(LED2-2)") (class "Default")
      (node (ref "LED2") (pin "BLUE") (pinfunction "2_BLUE") (pintype "passive"))
      (node (ref "R11") (pin "1") (pinfunction "1_1") (pintype "passive"))
    )
    (net (code "40") (name "Net-(LED2-3)") (class "Default")
      (node (ref "LED2") (pin "GREEN") (pinfunction "3_GREEN") (pintype "passive"))
      (node (ref "R9") (pin "1") (pinfunction "1_1") (pintype "passive"))
    )
    (net (code "41") (name "Net-(LED2-4)") (class "Default")
      (node (ref "LED2") (pin "RED") (pinfunction "4_RED") (pintype "passive"))
      (node (ref "R12") (pin "1") (pinfunction "1_1") (pintype "passive"))
    )
    (net (code "42") (name "Net-(R4-Pad2)") (class "Default")
      (node (ref "R4") (pin "2") (pinfunction "2_2") (pintype "passive"))
      (node (ref "RED_LED_0603") (pin "C") (pinfunction "C_C") (pintype "passive"))
    )
    (net (code "43") (name "Net-(U$1-INT)") (class "Default")
      (node (ref "R15") (pin "1") (pinfunction "1_1") (pintype "passive"))
      (node (ref "U$1") (pin "7") (pinfunction "INT_7") (pintype "bidirectional"))
    )
    (net (code "44") (name "Net-(U$1-OTG)") (class "Default")
      (node (ref "R16") (pin "1") (pinfunction "1_1") (pintype "passive"))
      (node (ref "U$1") (pin "8") (pinfunction "OTG_8") (pintype "bidirectional"))
    )
    (net (code "45") (name "Net-(U$1-TS)") (class "Default")
      (node (ref "R18") (pin "2") (pinfunction "2_2") (pintype "passive"))
      (node (ref "R19") (pin "1") (pinfunction "1_1") (pintype "passive"))
      (node (ref "R20") (pin "1") (pinfunction "1_1") (pintype "passive"))
      (node (ref "U$1") (pin "11") (pinfunction "TS_11") (pintype "bidirectional"))
    )
    (net (code "46") (name "Net-(U$1-~{PG})") (class "Default")
      (node (ref "R7") (pin "1") (pinfunction "1_1") (pintype "passive"))
      (node (ref "U$1") (pin "3") (pinfunction "~{PG}_3") (pintype "output"))
    )
    (net (code "47") (name "Net-(U$1-~{QON})") (class "Default")
      (node (ref "R20") (pin "2") (pinfunction "2_2") (pintype "passive"))
      (node (ref "U$1") (pin "12") (pinfunction "~{QON}_12") (pintype "bidirectional"))
    )
    (net (code "48") (name "Net-(U$5-PadB2)") (class "Default")
      (node (ref "U$5") (pin "B2") (pinfunction "B2_B2") (pintype "bidirectional"))
      (node (ref "U$6") (pin "1") (pinfunction "1_1") (pintype "passive"))
    )
    (net (code "49") (name "Net-(U3-VCAP_1)") (class "Default")
      (node (ref "C35") (pin "1") (pinfunction "1_1") (pintype "passive"))
      (node (ref "U3") (pin "31") (pinfunction "VCAP_1_31") (pintype "power_in"))
    )
    (net (code "50") (name "Net-(U3-VCAP_2)") (class "Default")
      (node (ref "C32") (pin "1") (pinfunction "1_1") (pintype "passive"))
      (node (ref "U3") (pin "47") (pinfunction "VCAP_2_47") (pintype "power_in"))
    )
    (net (code "51") (name "Net-(U4-CELL)") (class "Default")
      (node (ref "C39") (pin "1") (pinfunction "1_1") (pintype "passive"))
      (node (ref "R23") (pin "1") (pinfunction "1_1") (pintype "passive"))
      (node (ref "U4") (pin "2") (pinfunction "CELL_2") (pintype "bidirectional"))
    )
    (net (code "52") (name "Net-(U4-VDD)") (class "Default")
      (node (ref "C38") (pin "1") (pinfunction "1_1") (pintype "passive"))
      (node (ref "R22") (pin "1") (pinfunction "1_1") (pintype "passive"))
      (node (ref "U4") (pin "3") (pinfunction "VDD_3") (pintype "bidirectional"))
    )
    (net (code "53") (name "OSC32_IN_UC") (class "Default")
      (node (ref "C34") (pin "1") (pinfunction "1_1") (pintype "passive"))
      (node (ref "U3") (pin "3") (pinfunction "PC14_3") (pintype "bidirectional"))
      (node (ref "Y1") (pin "X1") (pinfunction "1_X1") (pintype "passive"))
    )
    (net (code "54") (name "OSC32_OUT_UC") (class "Default")
      (node (ref "C33") (pin "1") (pinfunction "1_1") (pintype "passive"))
      (node (ref "U3") (pin "4") (pinfunction "PC15_4") (pintype "bidirectional"))
      (node (ref "Y1") (pin "X2") (pinfunction "2_X2") (pintype "passive"))
    )
    (net (code "55") (name "OSC_IN_UC") (class "Default")
      (node (ref "C28") (pin "1") (pinfunction "1_1") (pintype "passive"))
      (node (ref "U3") (pin "5") (pinfunction "PH0/OSC_IN_5") (pintype "bidirectional"))
      (node (ref "Y2") (pin "1") (pinfunction "1_1") (pintype "passive"))
    )
    (net (code "56") (name "OSC_OUT_UC") (class "Default")
      (node (ref "C26") (pin "1") (pinfunction "1_1") (pintype "passive"))
      (node (ref "U3") (pin "6") (pinfunction "PH1/OSC_OUT_6") (pintype "bidirectional"))
      (node (ref "Y2") (pin "3") (pinfunction "2_3") (pintype "passive"))
    )
    (net (code "57") (name "PA8_PM_SCL") (class "Default")
      (node (ref "R14") (pin "1") (pinfunction "1_1") (pintype "passive"))
      (node (ref "U$1") (pin "5") (pinfunction "SCL_5") (pintype "output"))
      (node (ref "U3") (pin "41") (pinfunction "PA8_41") (pintype "bidirectional"))
      (node (ref "U4") (pin "7") (pinfunction "SCL_7") (pintype "bidirectional"))
    )
    (net (code "58") (name "PC9_PM_SDA") (class "Default")
      (node (ref "R13") (pin "1") (pinfunction "1_1") (pintype "passive"))
      (node (ref "U$1") (pin "6") (pinfunction "SDA_6") (pintype "bidirectional"))
      (node (ref "U3") (pin "40") (pinfunction "PC9_40") (pintype "bidirectional"))
      (node (ref "U4") (pin "8") (pinfunction "SDA_8") (pintype "bidirectional"))
    )
    (net (code "59") (name "PMID") (class "Default")
      (node (ref "C5") (pin "1") (pinfunction "1_1") (pintype "passive"))
      (node (ref "U$1") (pin "23") (pinfunction "PMID_23") (pintype "passive"))
    )
    (net (code "60") (name "PWR_UB") (class "Default")
      (node (ref "R1") (pin "1") (pinfunction "1_1") (pintype "passive"))
      (node (ref "U1") (pin "15") (pinfunction "PWR_ON_15") (pintype "bidirectional"))
      (node (ref "U5") (pin "4") (pinfunction "B_4") (pintype "bidirectional"))
    )
    (net (code "61") (name "PWR_UC") (class "Default")
      (node (ref "U3") (pin "28") (pinfunction "PB2_28") (pintype "bidirectional"))
      (node (ref "U5") (pin "2") (pinfunction "A_2") (pintype "bidirectional"))
    )
    (net (code "62") (name "REGN") (class "Default")
      (node (ref "C25") (pin "1") (pinfunction "1_1") (pintype "passive"))
      (node (ref "R18") (pin "1") (pinfunction "1_1") (pintype "passive"))
      (node (ref "U$1") (pin "22") (pinfunction "REGN_22") (pintype "bidirectional"))
    )
    (net (code "63") (name "RESET_UB") (class "Default")
      (node (ref "U1") (pin "18") (pinfunction "RESET_N_18") (pintype "bidirectional"))
      (node (ref "U6") (pin "4") (pinfunction "B_4") (pintype "bidirectional"))
    )
    (net (code "64") (name "RESET_UC") (class "Default")
      (node (ref "U3") (pin "24") (pinfunction "PC4_24") (pintype "bidirectional"))
      (node (ref "U6") (pin "2") (pinfunction "A_2") (pintype "bidirectional"))
    )
    (net (code "65") (name "RGB_BLUE") (class "Default")
      (node (ref "R11") (pin "2") (pinfunction "2_2") (pintype "passive"))
      (node (ref "U3") (pin "17") (pinfunction "PA3_17") (pintype "bidirectional"))
    )
    (net (code "66") (name "RGB_GREEN") (class "Default")
      (node (ref "R9") (pin "2") (pinfunction "2_2") (pintype "passive"))
      (node (ref "U3") (pin "16") (pinfunction "PA2_16") (pintype "bidirectional"))
    )
    (net (code "67") (name "RGB_RED") (class "Default")
      (node (ref "R12") (pin "2") (pinfunction "2_2") (pintype "passive"))
      (node (ref "U3") (pin "15") (pinfunction "PA1_15") (pintype "bidirectional"))
    )
    (net (code "68") (name "RI_UB") (class "Default")
      (node (ref "U1") (pin "7") (pinfunction "RI_7") (pintype "bidirectional"))
      (node (ref "U8") (pin "14") (pinfunction "1B2_14") (pintype "bidirectional"))
    )
    (net (code "69") (name "RI_UC") (class "Default")
      (node (ref "U3") (pin "33") (pinfunction "PB12_33") (pintype "bidirectional"))
      (node (ref "U8") (pin "7") (pinfunction "1A2_7") (pintype "bidirectional"))
    )
    (net (code "70") (name "RTS_UB") (class "Default")
      (node (ref "U1") (pin "10") (pinfunction "RTS_10") (pintype "bidirectional"))
      (node (ref "U2") (pin "15") (pinfunction "1B1_15") (pintype "bidirectional"))
    )
    (net (code "71") (name "RTS_UC") (class "Default")
      (node (ref "U2") (pin "6") (pinfunction "1A1_6") (pintype "bidirectional"))
      (node (ref "U3") (pin "35") (pinfunction "PB14_35") (pintype "bidirectional"))
    )
    (net (code "72") (name "RX") (class "Default")
      (node (ref "JP1") (pin "4") (pinfunction "4_4") (pintype "passive"))
      (node (ref "U3") (pin "43") (pinfunction "PA10_43") (pintype "bidirectional"))
    )
    (net (code "73") (name "RXD_UB") (class "Default")
      (node (ref "U1") (pin "13") (pinfunction "RXD_13") (pintype "bidirectional"))
      (node (ref "U8") (pin "13") (pinfunction "2B1_13") (pintype "bidirectional"))
    )
    (net (code "74") (name "RXD_UC") (class "Default")
      (node (ref "U3") (pin "30") (pinfunction "PB11_30") (pintype "bidirectional"))
      (node (ref "U8") (pin "8") (pinfunction "2A1_8") (pintype "bidirectional"))
    )
    (net (code "75") (name "SIM_CLK") (class "Default")
      (node (ref "C12") (pin "1") (pinfunction "1_1") (pintype "passive"))
      (node (ref "J1") (pin "C3") (pinfunction "CLK_C3") (pintype "passive"))
      (node (ref "U1") (pin "38") (pinfunction "SIM_CLK_38") (pintype "bidirectional"))
    )
    (net (code "76") (name "SIM_DET") (class "Default")
      (node (ref "U1") (pin "42") (pinfunction "SIM_DET_42") (pintype "bidirectional"))
    )
    (net (code "77") (name "SIM_IO") (class "Default")
      (node (ref "C13") (pin "1") (pinfunction "1_1") (pintype "passive"))
      (node (ref "J1") (pin "C7") (pinfunction "I/O_C7") (pintype "passive"))
      (node (ref "U1") (pin "39") (pinfunction "SIM_IO_39") (pintype "bidirectional"))
    )
    (net (code "78") (name "SIM_RST") (class "Default")
      (node (ref "C10") (pin "1") (pinfunction "1_1") (pintype "passive"))
      (node (ref "J1") (pin "C2") (pinfunction "RST_C2") (pintype "passive"))
      (node (ref "U1") (pin "40") (pinfunction "SIM_RST_40") (pintype "bidirectional"))
    )
    (net (code "79") (name "SIM_VCC") (class "Default")
      (node (ref "C11") (pin "1") (pinfunction "1_1") (pintype "passive"))
      (node (ref "C14") (pin "1") (pinfunction "1_1") (pintype "passive"))
      (node (ref "J1") (pin "C1") (pinfunction "VCC_C1") (pintype "passive"))
      (node (ref "J1") (pin "C6") (pinfunction "VPP_C6") (pintype "passive"))
      (node (ref "U1") (pin "41") (pinfunction "VSIM_41") (pintype "bidirectional"))
    )
    (net (code "80") (name "STAT") (class "Default")
      (node (ref "R4") (pin "1") (pinfunction "1_1") (pintype "passive"))
      (node (ref "U$1") (pin "4") (pinfunction "STAT_4") (pintype "bidirectional"))
    )
    (net (code "81") (name "SW") (class "Default")
      (node (ref "C7") (pin "2") (pinfunction "2_2") (pintype "passive"))
      (node (ref "U$1") (pin "19") (pinfunction "SW_19") (pintype "power_in"))
      (node (ref "U$1") (pin "20") (pinfunction "SW_20") (pintype "power_in"))
      (node (ref "U$4") (pin "P$1") (pinfunction "1_P$1") (pintype "bidirectional"))
    )
    (net (code "82") (name "TX") (class "Default")
      (node (ref "JP1") (pin "3") (pinfunction "3_3") (pintype "passive"))
      (node (ref "U3") (pin "42") (pinfunction "PA9_42") (pintype "bidirectional"))
    )
    (net (code "83") (name "TXD_UB") (class "Default")
      (node (ref "U1") (pin "12") (pinfunction "TXD_12") (pintype "bidirectional"))
      (node (ref "U2") (pin "14") (pinfunction "1B2_14") (pintype "bidirectional"))
    )
    (net (code "84") (name "TXD_UC") (class "Default")
      (node (ref "U2") (pin "7") (pinfunction "1A2_7") (pintype "bidirectional"))
      (node (ref "U3") (pin "29") (pinfunction "PB10_29") (pintype "bidirectional"))
    )
    (net (code "85") (name "USB_DM") (class "Default")
      (node (ref "R6") (pin "2") (pinfunction "2_2") (pintype "passive"))
      (node (ref "R7") (pin "2") (pinfunction "2_2") (pintype "passive"))
      (node (ref "U$7") (pin "P$2") (pinfunction "P$2_P$2") (pintype "bidirectional"))
      (node (ref "X1") (pin "D-") (pinfunction "D-_D-") (pintype "bidirectional"))
    )
    (net (code "86") (name "USB_DM_UC") (class "Default")
      (node (ref "R6") (pin "1") (pinfunction "1_1") (pintype "passive"))
      (node (ref "U3") (pin "44") (pinfunction "PA11_44") (pintype "bidirectional"))
    )
    (net (code "87") (name "USB_DP") (class "Default")
      (node (ref "R5") (pin "2") (pinfunction "2_2") (pintype "passive"))
      (node (ref "U$1") (pin "2") (pinfunction "PSEL_2") (pintype "output"))
      (node (ref "U$7") (pin "P$1") (pinfunction "P$1_P$1") (pintype "bidirectional"))
      (node (ref "X1") (pin "D+") (pinfunction "D+_D+") (pintype "bidirectional"))
    )
    (net (code "88") (name "USB_DP_UC") (class "Default")
      (node (ref "R5") (pin "1") (pinfunction "1_1") (pintype "passive"))
      (node (ref "U3") (pin "45") (pinfunction "PA12_45") (pintype "bidirectional"))
    )
    (net (code "89") (name "VBAT") (class "Default")
      (node (ref "JP2") (pin "3") (pinfunction "3_3") (pintype "passive"))
      (node (ref "U3") (pin "1") (pinfunction "VBAT_1") (pintype "power_in"))
    )
    (net (code "90") (name "VBUS") (class "Default")
      (node (ref "U$3") (pin "ANODE") (pinfunction "ANODE_ANODE") (pintype "bidirectional"))
      (node (ref "X1") (pin "VBUS") (pinfunction "VBUS_VBUS") (pintype "bidirectional"))
    )
    (net (code "91") (name "VIN") (class "Default")
      (node (ref "C4") (pin "1") (pinfunction "1_1") (pintype "passive"))
      (node (ref "JP1") (pin "1") (pinfunction "1_1") (pintype "passive"))
      (node (ref "U$1") (pin "1") (pinfunction "VBUS_1") (pintype "power_in"))
      (node (ref "U$1") (pin "24") (pinfunction "VBUS_24") (pintype "passive"))
      (node (ref "U$3") (pin "CATHODE") (pinfunction "CATHODE_CATHODE") (pintype "bidirectional"))
    )
    (net (code "92") (name "V_BCKP") (class "Default")
      (node (ref "R1") (pin "2") (pinfunction "2_2") (pintype "passive"))
      (node (ref "U1") (pin "2") (pinfunction "V_BCKP_2") (pintype "bidirectional"))
    )
    (net (code "93") (name "V_INT") (class "Default")
      (node (ref "C21") (pin "1") (pinfunction "1_1") (pintype "passive"))
      (node (ref "C22") (pin "1") (pinfunction "1_1") (pintype "passive"))
      (node (ref "U1") (pin "4") (pinfunction "V_INT_4") (pintype "bidirectional"))
      (node (ref "U2") (pin "2") (pinfunction "VCCB_2") (pintype "bidirectional"))
      (node (ref "U8") (pin "2") (pinfunction "VCCB_2") (pintype "bidirectional"))
    )
    (net (code "94") (name "WKP") (class "Default")
      (node (ref "JP1") (pin "5") (pinfunction "5_5") (pintype "passive"))
      (node (ref "U3") (pin "14") (pinfunction "WKUP/PA0_14") (pintype "bidirectional"))
    )
    (net (code "95") (name "unconnected-(MODE-Pad4)") (class "Default")
      (node (ref "MODE") (pin "4") (pinfunction "4_4") (pintype "passive"))
    )
    (net (code "96") (name "unconnected-(RESET-Pad1)") (class "Default")
      (node (ref "RESET") (pin "1") (pinfunction "1_1") (pintype "passive"))
    )
    (net (code "97") (name "unconnected-(U1-DCD-Pad8)") (class "Default")
      (node (ref "U1") (pin "8") (pinfunction "DCD_8") (pintype "bidirectional"))
    )
    (net (code "98") (name "unconnected-(U1-DSR-Pad6)") (class "Default")
      (node (ref "U1") (pin "6") (pinfunction "DSR_6") (pintype "bidirectional"))
    )
    (net (code "99") (name "unconnected-(U1-GPIO1-Pad16)") (class "Default")
      (node (ref "U1") (pin "16") (pinfunction "GPIO1_16") (pintype "bidirectional"))
    )
    (net (code "100") (name "unconnected-(U1-GPIO2-Pad23)") (class "Default")
      (node (ref "U1") (pin "23") (pinfunction "GPIO2_23") (pintype "bidirectional"))
    )
    (net (code "101") (name "unconnected-(U1-GPIO3-Pad24)") (class "Default")
      (node (ref "U1") (pin "24") (pinfunction "GPIO3_24") (pintype "bidirectional"))
    )
    (net (code "102") (name "unconnected-(U1-GPIO4-Pad25)") (class "Default")
      (node (ref "U1") (pin "25") (pinfunction "GPIO4_25") (pintype "bidirectional"))
    )
    (net (code "103") (name "unconnected-(U1-I2S_CLK-Pad36)") (class "Default")
      (node (ref "U1") (pin "36") (pinfunction "I2S_CLK_36") (pintype "bidirectional"))
    )
    (net (code "104") (name "unconnected-(U1-I2S_RXD-Pad37)") (class "Default")
      (node (ref "U1") (pin "37") (pinfunction "I2S_RXD_37") (pintype "bidirectional"))
    )
    (net (code "105") (name "unconnected-(U1-I2S_TXD-Pad35)") (class "Default")
      (node (ref "U1") (pin "35") (pinfunction "I2S_TXD_35") (pintype "bidirectional"))
    )
    (net (code "106") (name "unconnected-(U1-I2S_WA-Pad34)") (class "Default")
      (node (ref "U1") (pin "34") (pinfunction "I2S_WA_34") (pintype "bidirectional"))
    )
    (net (code "107") (name "unconnected-(U1-MIC_BIAS-Pad46)") (class "Default")
      (node (ref "U1") (pin "46") (pinfunction "MIC_BIAS_46") (pintype "bidirectional"))
    )
    (net (code "108") (name "unconnected-(U1-MIC_GND-Pad47)") (class "Default")
      (node (ref "U1") (pin "47") (pinfunction "MIC_GND_47") (pintype "bidirectional"))
    )
    (net (code "109") (name "unconnected-(U1-MIC_N-Pad48)") (class "Default")
      (node (ref "U1") (pin "48") (pinfunction "MIC_N_48") (pintype "bidirectional"))
    )
    (net (code "110") (name "unconnected-(U1-MIC_P-Pad49)") (class "Default")
      (node (ref "U1") (pin "49") (pinfunction "MIC_P_49") (pintype "bidirectional"))
    )
    (net (code "111") (name "unconnected-(U1-RSVD-Pad19)") (class "Default")
      (node (ref "U1") (pin "19") (pinfunction "RSVD_19") (pintype "bidirectional"))
    )
    (net (code "112") (name "unconnected-(U1-RSVD-Pad31)") (class "Default")
      (node (ref "U1") (pin "31") (pinfunction "RSVD_31") (pintype "bidirectional"))
    )
    (net (code "113") (name "unconnected-(U1-RXD_AUX{slash}USB_D--Pad28)") (class "Default")
      (node (ref "U1") (pin "28") (pinfunction "RXD_AUX/USB_D-_28") (pintype "bidirectional"))
    )
    (net (code "114") (name "unconnected-(U1-SCL-Pad27)") (class "Default")
      (node (ref "U1") (pin "27") (pinfunction "SCL_27") (pintype "bidirectional"))
    )
    (net (code "115") (name "unconnected-(U1-SDA-Pad26)") (class "Default")
      (node (ref "U1") (pin "26") (pinfunction "SDA_26") (pintype "bidirectional"))
    )
    (net (code "116") (name "unconnected-(U1-SPK_N-Pad45)") (class "Default")
      (node (ref "U1") (pin "45") (pinfunction "SPK_N_45") (pintype "bidirectional"))
    )
    (net (code "117") (name "unconnected-(U1-SPK_P-Pad44)") (class "Default")
      (node (ref "U1") (pin "44") (pinfunction "SPK_P_44") (pintype "bidirectional"))
    )
    (net (code "118") (name "unconnected-(U1-TXD_AUX{slash}USB_D+-Pad29)") (class "Default")
      (node (ref "U1") (pin "29") (pinfunction "TXD_AUX/USB_D+_29") (pintype "bidirectional"))
    )
    (net (code "119") (name "unconnected-(U1-VUSB_DET-Pad17)") (class "Default")
      (node (ref "U1") (pin "17") (pinfunction "VUSB_DET_17") (pintype "bidirectional"))
    )
    (net (code "120") (name "unconnected-(U2-2A1-Pad8)") (class "Default")
      (node (ref "U2") (pin "8") (pinfunction "2A1_8") (pintype "bidirectional"))
    )
    (net (code "121") (name "unconnected-(U2-2A2-Pad9)") (class "Default")
      (node (ref "U2") (pin "9") (pinfunction "2A2_9") (pintype "bidirectional"))
    )
    (net (code "122") (name "unconnected-(U2-2B1-Pad13)") (class "Default")
      (node (ref "U2") (pin "13") (pinfunction "2B1_13") (pintype "bidirectional"))
    )
    (net (code "123") (name "unconnected-(U2-2B2-Pad12)") (class "Default")
      (node (ref "U2") (pin "12") (pinfunction "2B2_12") (pintype "bidirectional"))
    )
    (net (code "124") (name "unconnected-(U8-2A2-Pad9)") (class "Default")
      (node (ref "U8") (pin "9") (pinfunction "2A2_9") (pintype "bidirectional"))
    )
    (net (code "125") (name "unconnected-(U8-2B2-Pad12)") (class "Default")
      (node (ref "U8") (pin "12") (pinfunction "2B2_12") (pintype "bidirectional"))
    )
    (net (code "126") (name "~{CE}") (class "Default")
      (node (ref "R17") (pin "1") (pinfunction "1_1") (pintype "passive"))
      (node (ref "U$1") (pin "9") (pinfunction "~{CE}_9") (pintype "output"))
    )
    (net (code "127") (name "~{LOW_BAT_INT_UC}") (class "Default")
      (node (ref "R21") (pin "1") (pinfunction "1_1") (pintype "passive"))
      (node (ref "U3") (pin "2") (pinfunction "PC13_2") (pintype "bidirectional"))
      (node (ref "U4") (pin "5") (pinfunction "ALT_5") (pintype "bidirectional"))
    )
    (net (code "128") (name "~{LVLOE_UC}") (class "Default")
      (node (ref "R3") (pin "1") (pinfunction "1_1") (pintype "passive"))
      (node (ref "U2") (pin "1") (pinfunction "1/OE_1") (pintype "bidirectional"))
      (node (ref "U2") (pin "16") (pinfunction "2/OE_16") (pintype "bidirectional"))
      (node (ref "U3") (pin "36") (pinfunction "PB15_36") (pintype "bidirectional"))
      (node (ref "U8") (pin "1") (pinfunction "1/OE_1") (pintype "bidirectional"))
      (node (ref "U8") (pin "16") (pinfunction "2/OE_16") (pintype "bidirectional"))
    )
    (net (code "129") (name "~{MODE}") (class "Default")
      (node (ref "MODE") (pin "3") (pinfunction "3_3") (pintype "passive"))
      (node (ref "U3") (pin "38") (pinfunction "PC7_38") (pintype "bidirectional"))
    )
    (net (code "130") (name "~{RST}") (class "Default")
      (node (ref "C6") (pin "1") (pinfunction "1_1") (pintype "passive"))
      (node (ref "JP2") (pin "2") (pinfunction "2_2") (pintype "passive"))
      (node (ref "R8") (pin "1") (pinfunction "1_1") (pintype "passive"))
      (node (ref "RESET") (pin "2") (pinfunction "2_2") (pintype "passive"))
      (node (ref "U3") (pin "7") (pinfunction "NRST_7") (pintype "power_in"))
    )
  )
)
